# moire_v1_4-wip.net
KiCad netlist of a schematic drawn in EAGLE
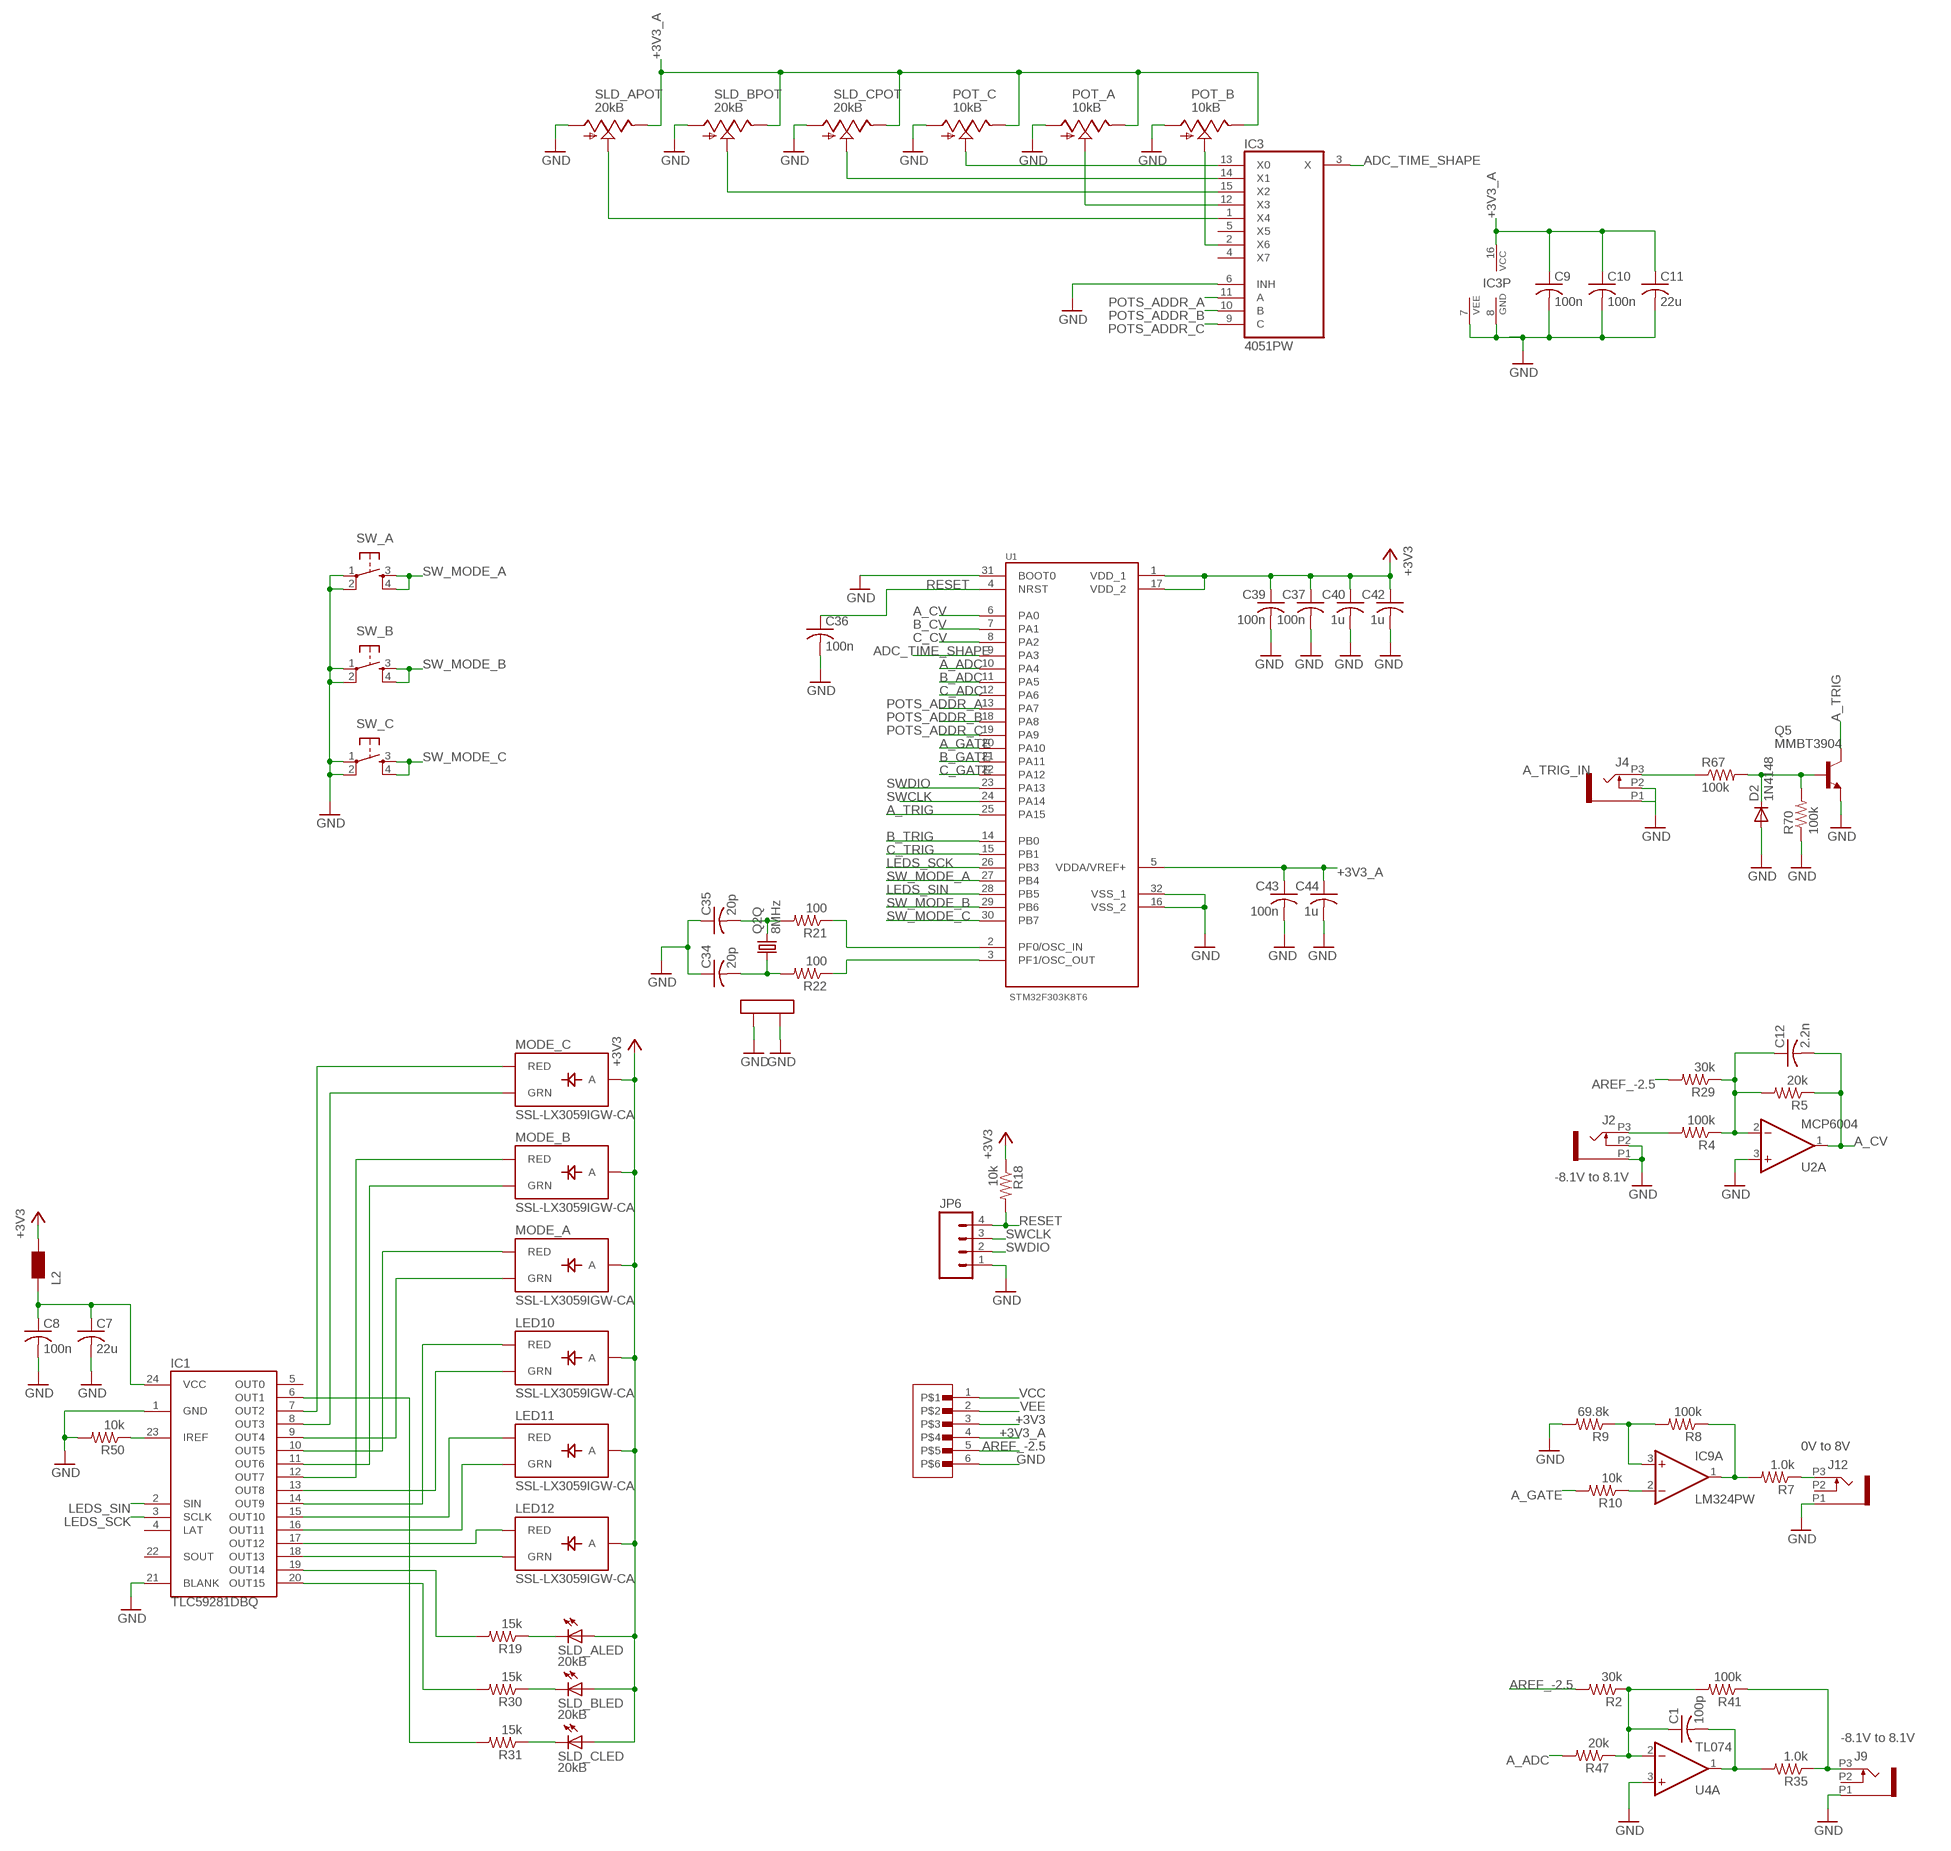
[diagram p0: schematic, sheet 1, part 1 of 2]
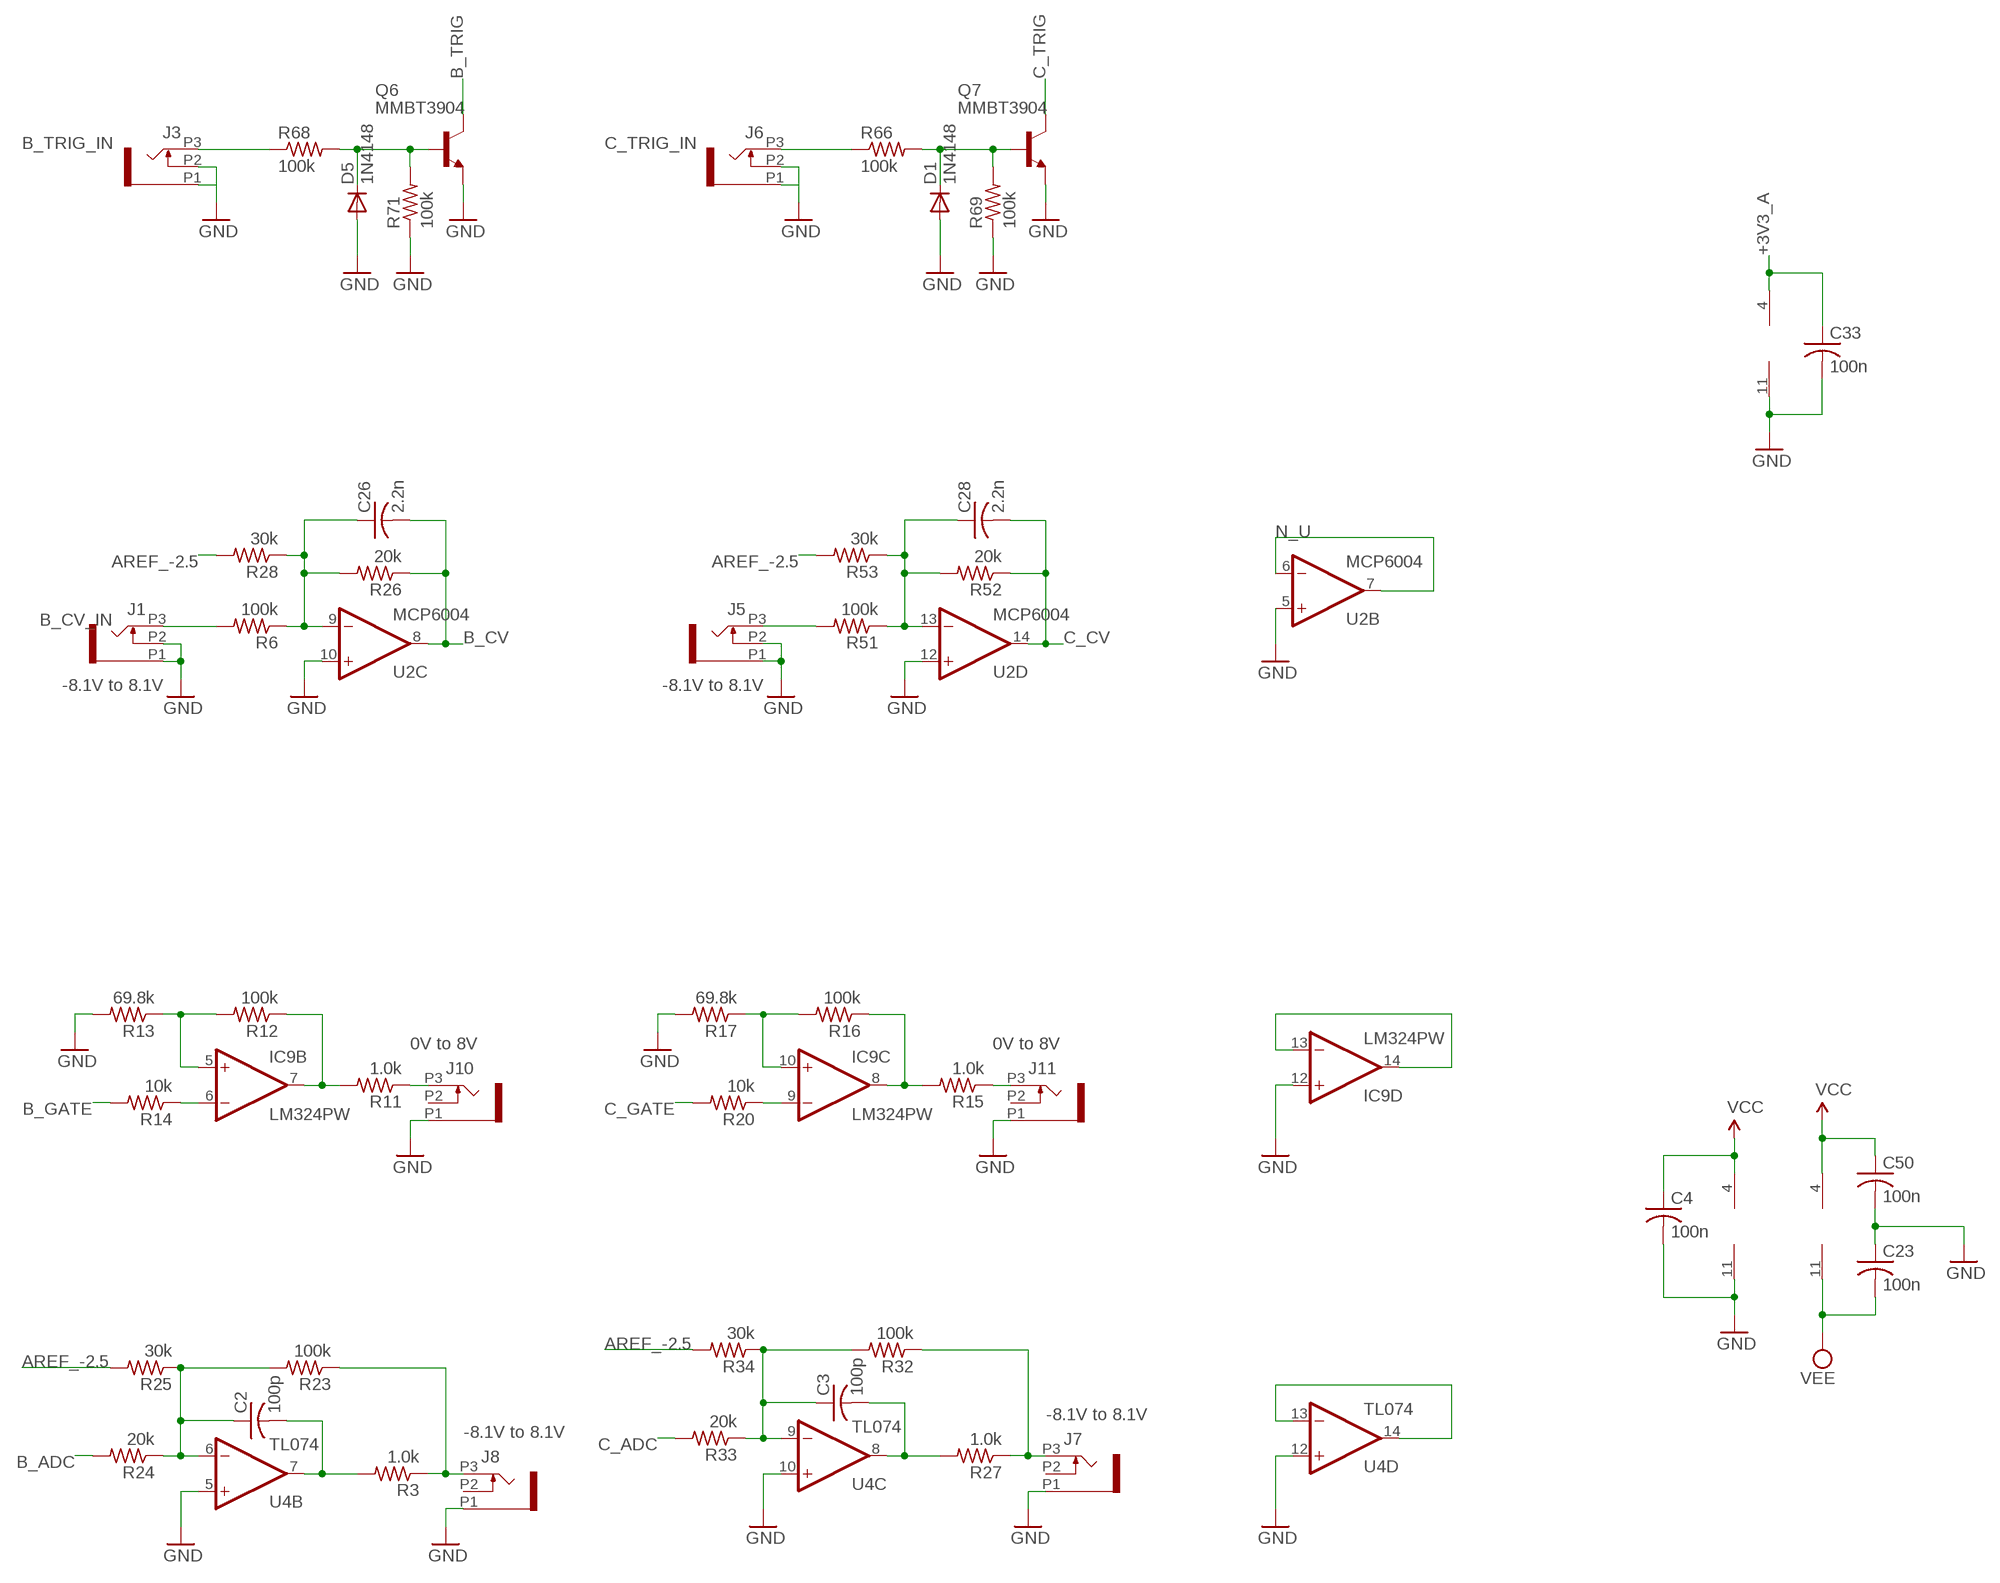
[diagram p1: schematic, sheet 1, part 2 of 2]
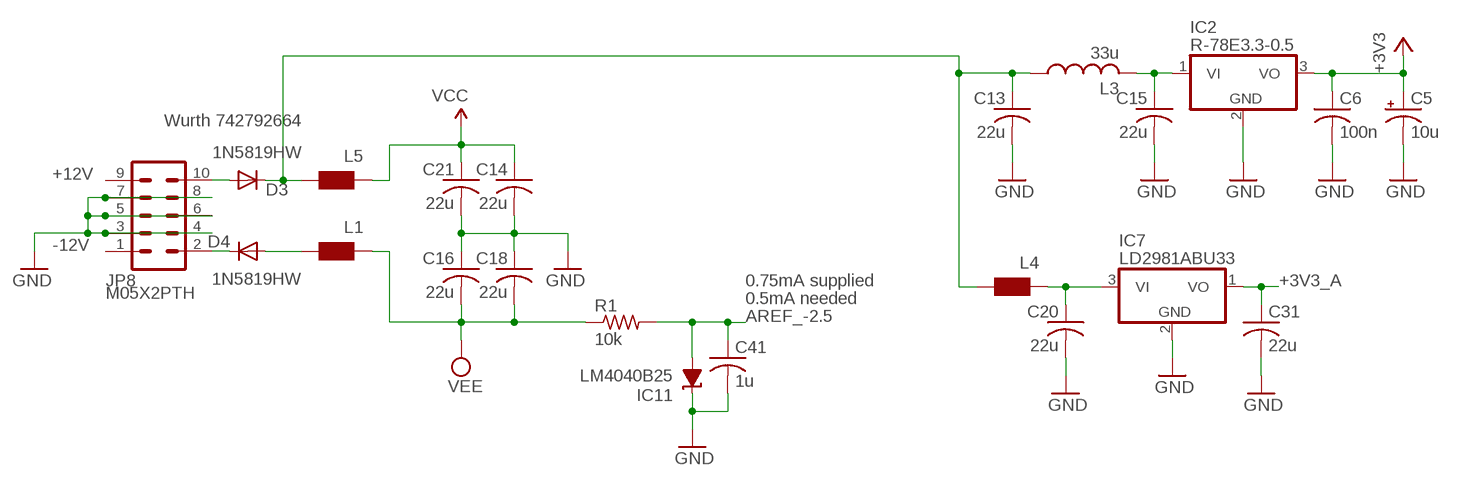
[diagram p2: schematic, sheet 2]

(export (version "E")
  (design (tool "Eeschema 10.0.6"))
  (components
    (comp (ref "C5")
      (value "10u")
      (footprint "eagle-import:PANASONIC_A")
      (libsource (lib "eagle-import") (part "CPOL-USA"))
    )
    (comp (ref "C6")
      (value "100n")
      (footprint "eagle-import:C0603")
      (libsource (lib "eagle-import") (part "C-USC0603"))
    )
    (comp (ref "C13")
      (value "22u")
      (footprint "eagle-import:C1206")
      (libsource (lib "eagle-import") (part "C-USC1206"))
    )
    (comp (ref "C14")
      (value "22u")
      (footprint "eagle-import:C1206")
      (libsource (lib "eagle-import") (part "C-USC1206"))
    )
    (comp (ref "C15")
      (value "22u")
      (footprint "eagle-import:C1206")
      (libsource (lib "eagle-import") (part "C-USC1206"))
    )
    (comp (ref "C16")
      (value "22u")
      (footprint "eagle-import:C1206")
      (libsource (lib "eagle-import") (part "C-USC1206"))
    )
    (comp (ref "C18")
      (value "22u")
      (footprint "eagle-import:C1206")
      (libsource (lib "eagle-import") (part "C-USC1206"))
    )
    (comp (ref "C20")
      (value "22u")
      (footprint "eagle-import:C1206")
      (libsource (lib "eagle-import") (part "C-USC1206"))
    )
    (comp (ref "C21")
      (value "22u")
      (footprint "eagle-import:C1206")
      (libsource (lib "eagle-import") (part "C-USC1206"))
    )
    (comp (ref "C31")
      (value "22u")
      (footprint "eagle-import:C1206")
      (libsource (lib "eagle-import") (part "C-USC1206"))
    )
    (comp (ref "C41")
      (value "1u")
      (footprint "eagle-import:C0603")
      (libsource (lib "eagle-import") (part "C-USC0603"))
    )
    (comp (ref "D3")
      (value "1N5819HW")
      (footprint "eagle-import:SOD123")
      (libsource (lib "eagle-import") (part "DIODE-SOD123"))
    )
    (comp (ref "D4")
      (value "1N5819HW")
      (footprint "eagle-import:SOD123")
      (libsource (lib "eagle-import") (part "DIODE-SOD123"))
    )
    (comp (ref "IC2")
      (value "R-78E3.3-0.5")
      (footprint "eagle-import:WE78")
      (libsource (lib "eagle-import") (part "WE173950378"))
    )
    (comp (ref "IC7")
      (value "LD2981ABU33")
      (footprint "eagle-import:SOT89")
      (libsource (lib "eagle-import") (part "LD2981ABU"))
    )
    (comp (ref "IC11")
      (value "LM4040B25")
      (footprint "eagle-import:DBZ_R-PDSO-G3")
      (libsource (lib "eagle-import") (part "LM4041DBZB12"))
    )
    (comp (ref "JP8")
      (value "M05X2PTH")
      (footprint "eagle-import:2X5-PTH")
      (libsource (lib "eagle-import") (part "M05X2PTH"))
    )
    (comp (ref "L1")
      (value "WE-CBF_0603")
      (footprint "eagle-import:0603")
      (libsource (lib "eagle-import") (part "WE-CBF_0603"))
    )
    (comp (ref "L3")
      (value "33u")
      (footprint "eagle-import:L2012C")
      (libsource (lib "eagle-import") (part "L-USL2012C"))
    )
    (comp (ref "L4")
      (value "WE-CBF_0603")
      (footprint "eagle-import:0603")
      (libsource (lib "eagle-import") (part "WE-CBF_0603"))
    )
    (comp (ref "L5")
      (value "WE-CBF_0603")
      (footprint "eagle-import:0603")
      (libsource (lib "eagle-import") (part "WE-CBF_0603"))
    )
    (comp (ref "R1")
      (value "10k")
      (footprint "eagle-import:R0603")
      (libsource (lib "eagle-import") (part "R-US_R0603"))
    )
    (comp (ref "C1")
      (value "100p")
      (footprint "eagle-import:C0603")
      (libsource (lib "eagle-import") (part "C-USC0603"))
    )
    (comp (ref "C2")
      (value "100p")
      (footprint "eagle-import:C0603")
      (libsource (lib "eagle-import") (part "C-USC0603"))
    )
    (comp (ref "C3")
      (value "100p")
      (footprint "eagle-import:C0603")
      (libsource (lib "eagle-import") (part "C-USC0603"))
    )
    (comp (ref "C4")
      (value "100n")
      (footprint "eagle-import:C0603")
      (libsource (lib "eagle-import") (part "C-USC0603"))
    )
    (comp (ref "C7")
      (value "22u")
      (footprint "eagle-import:C1206")
      (libsource (lib "eagle-import") (part "C-USC1206"))
    )
    (comp (ref "C8")
      (value "100n")
      (footprint "eagle-import:C0603")
      (libsource (lib "eagle-import") (part "C-USC0603"))
    )
    (comp (ref "C9")
      (value "100n")
      (footprint "eagle-import:C0603")
      (libsource (lib "eagle-import") (part "C-USC0603"))
    )
    (comp (ref "C10")
      (value "100n")
      (footprint "eagle-import:C0603")
      (libsource (lib "eagle-import") (part "C-USC0603"))
    )
    (comp (ref "C11")
      (value "22u")
      (footprint "eagle-import:C1206")
      (libsource (lib "eagle-import") (part "C-USC1206"))
    )
    (comp (ref "C12")
      (value "2.2n")
      (footprint "eagle-import:C0603")
      (libsource (lib "eagle-import") (part "C-USC0603"))
    )
    (comp (ref "C23")
      (value "100n")
      (footprint "eagle-import:C0603")
      (libsource (lib "eagle-import") (part "C-USC0603"))
    )
    (comp (ref "C26")
      (value "2.2n")
      (footprint "eagle-import:C0603")
      (libsource (lib "eagle-import") (part "C-USC0603"))
    )
    (comp (ref "C28")
      (value "2.2n")
      (footprint "eagle-import:C0603")
      (libsource (lib "eagle-import") (part "C-USC0603"))
    )
    (comp (ref "C33")
      (value "100n")
      (footprint "eagle-import:C0603")
      (libsource (lib "eagle-import") (part "C-USC0603"))
    )
    (comp (ref "C34")
      (value "20p")
      (footprint "eagle-import:C0603")
      (libsource (lib "eagle-import") (part "C-USC0603"))
    )
    (comp (ref "C35")
      (value "20p")
      (footprint "eagle-import:C0603")
      (libsource (lib "eagle-import") (part "C-USC0603"))
    )
    (comp (ref "C36")
      (value "100n")
      (footprint "eagle-import:C0603")
      (libsource (lib "eagle-import") (part "C-USC0603"))
    )
    (comp (ref "C37")
      (value "100n")
      (footprint "eagle-import:C0603")
      (libsource (lib "eagle-import") (part "C-USC0603"))
    )
    (comp (ref "C39")
      (value "100n")
      (footprint "eagle-import:C0603")
      (libsource (lib "eagle-import") (part "C-USC0603"))
    )
    (comp (ref "C40")
      (value "1u")
      (footprint "eagle-import:C0603")
      (libsource (lib "eagle-import") (part "C-USC0603"))
    )
    (comp (ref "C42")
      (value "1u")
      (footprint "eagle-import:C0603")
      (libsource (lib "eagle-import") (part "C-USC0603"))
    )
    (comp (ref "C43")
      (value "100n")
      (footprint "eagle-import:C0603")
      (libsource (lib "eagle-import") (part "C-USC0603"))
    )
    (comp (ref "C44")
      (value "1u")
      (footprint "eagle-import:C0603")
      (libsource (lib "eagle-import") (part "C-USC0603"))
    )
    (comp (ref "C50")
      (value "100n")
      (footprint "eagle-import:C0603")
      (libsource (lib "eagle-import") (part "C-USC0603"))
    )
    (comp (ref "D1")
      (value "1N4148")
      (footprint "eagle-import:SOD523")
      (libsource (lib "eagle-import") (part "DIODE-SOD523"))
    )
    (comp (ref "D2")
      (value "1N4148")
      (footprint "eagle-import:SOD523")
      (libsource (lib "eagle-import") (part "DIODE-SOD523"))
    )
    (comp (ref "D5")
      (value "1N4148")
      (footprint "eagle-import:SOD523")
      (libsource (lib "eagle-import") (part "DIODE-SOD523"))
    )
    (comp (ref "IC1")
      (value "TLC59281DBQ")
      (footprint "eagle-import:TSSOP24_0635")
      (libsource (lib "eagle-import") (part "TLC59281DBQ"))
    )
    (comp (ref "IC3")
      (value "4051PW")
      (footprint "eagle-import:TSSOP16_065")
      (libsource (lib "eagle-import") (part "4051PW"))
    )
    (comp (ref "IC9")
      (value "LM324PW")
      (footprint "eagle-import:TSSOP14_065")
      (libsource (lib "eagle-import") (part "TL074PW"))
    )
    (comp (ref "J1")
      (value "PJ301_THONKICONN6")
      (footprint "eagle-import:WQP_PJ_301M6")
      (libsource (lib "eagle-import") (part "PJ301_THONKICONN6"))
    )
    (comp (ref "J2")
      (value "PJ301_THONKICONN6")
      (footprint "eagle-import:WQP_PJ_301M6")
      (libsource (lib "eagle-import") (part "PJ301_THONKICONN6"))
    )
    (comp (ref "J3")
      (value "PJ301_THONKICONN6")
      (footprint "eagle-import:WQP_PJ_301M6")
      (libsource (lib "eagle-import") (part "PJ301_THONKICONN6"))
    )
    (comp (ref "J4")
      (value "PJ301_THONKICONN6")
      (footprint "eagle-import:WQP_PJ_301M6")
      (libsource (lib "eagle-import") (part "PJ301_THONKICONN6"))
    )
    (comp (ref "J5")
      (value "PJ301_THONKICONN6")
      (footprint "eagle-import:WQP_PJ_301M6")
      (libsource (lib "eagle-import") (part "PJ301_THONKICONN6"))
    )
    (comp (ref "J6")
      (value "PJ301_THONKICONN6")
      (footprint "eagle-import:WQP_PJ_301M6")
      (libsource (lib "eagle-import") (part "PJ301_THONKICONN6"))
    )
    (comp (ref "J7")
      (value "PJ301_THONKICONN6")
      (footprint "eagle-import:WQP_PJ_301M6")
      (libsource (lib "eagle-import") (part "PJ301_THONKICONN6"))
    )
    (comp (ref "J8")
      (value "PJ301_THONKICONN6")
      (footprint "eagle-import:WQP_PJ_301M6")
      (libsource (lib "eagle-import") (part "PJ301_THONKICONN6"))
    )
    (comp (ref "J9")
      (value "PJ301_THONKICONN6")
      (footprint "eagle-import:WQP_PJ_301M6")
      (libsource (lib "eagle-import") (part "PJ301_THONKICONN6"))
    )
    (comp (ref "J10")
      (value "PJ301_THONKICONN6")
      (footprint "eagle-import:WQP_PJ_301M6")
      (libsource (lib "eagle-import") (part "PJ301_THONKICONN6"))
    )
    (comp (ref "J11")
      (value "PJ301_THONKICONN6")
      (footprint "eagle-import:WQP_PJ_301M6")
      (libsource (lib "eagle-import") (part "PJ301_THONKICONN6"))
    )
    (comp (ref "J12")
      (value "PJ301_THONKICONN6")
      (footprint "eagle-import:WQP_PJ_301M6")
      (libsource (lib "eagle-import") (part "PJ301_THONKICONN6"))
    )
    (comp (ref "JP6")
      (value "M04PTH")
      (footprint "eagle-import:1X04")
      (libsource (lib "eagle-import") (part "M04PTH"))
    )
    (comp (ref "L2")
      (value "WE-CBF_0603")
      (footprint "eagle-import:0603")
      (libsource (lib "eagle-import") (part "WE-CBF_0603"))
    )
    (comp (ref "LED10")
      (value "SSL-LX3059IGW-CA")
      (footprint "eagle-import:LED-BICOLOR-THROUGHHOLE-LUMEX")
      (libsource (lib "eagle-import") (part "LED-BICOLOR-THROUGHHOLE-CA"))
    )
    (comp (ref "LED11")
      (value "SSL-LX3059IGW-CA")
      (footprint "eagle-import:LED-BICOLOR-THROUGHHOLE-LUMEX")
      (libsource (lib "eagle-import") (part "LED-BICOLOR-THROUGHHOLE-CA"))
    )
    (comp (ref "LED12")
      (value "SSL-LX3059IGW-CA")
      (footprint "eagle-import:LED-BICOLOR-THROUGHHOLE-LUMEX")
      (libsource (lib "eagle-import") (part "LED-BICOLOR-THROUGHHOLE-CA"))
    )
    (comp (ref "MODE_A")
      (value "SSL-LX3059IGW-CA")
      (footprint "eagle-import:LED-BICOLOR-THROUGHHOLE-LUMEX")
      (libsource (lib "eagle-import") (part "LED-BICOLOR-THROUGHHOLE-CA"))
    )
    (comp (ref "MODE_B")
      (value "SSL-LX3059IGW-CA")
      (footprint "eagle-import:LED-BICOLOR-THROUGHHOLE-LUMEX")
      (libsource (lib "eagle-import") (part "LED-BICOLOR-THROUGHHOLE-CA"))
    )
    (comp (ref "MODE_C")
      (value "SSL-LX3059IGW-CA")
      (footprint "eagle-import:LED-BICOLOR-THROUGHHOLE-LUMEX")
      (libsource (lib "eagle-import") (part "LED-BICOLOR-THROUGHHOLE-CA"))
    )
    (comp (ref "POT_A")
      (value "10kB")
      (footprint "eagle-import:ALPS_POT_VERTICAL")
      (libsource (lib "eagle-import") (part "POT_USVERTICAL"))
    )
    (comp (ref "POT_B")
      (value "10kB")
      (footprint "eagle-import:ALPS_POT_VERTICAL")
      (libsource (lib "eagle-import") (part "POT_USVERTICAL"))
    )
    (comp (ref "POT_C")
      (value "10kB")
      (footprint "eagle-import:ALPS_POT_VERTICAL")
      (libsource (lib "eagle-import") (part "POT_USVERTICAL"))
    )
    (comp (ref "Q2")
      (value "8MHz")
      (footprint "eagle-import:CTS406")
      (libsource (lib "eagle-import") (part "CRYSTAL"))
    )
    (comp (ref "Q5")
      (value "MMBT3904")
      (footprint "eagle-import:SOT23-BEC")
      (libsource (lib "eagle-import") (part "-NPN-SOT23-BECMMBT3904LT1"))
    )
    (comp (ref "Q6")
      (value "MMBT3904")
      (footprint "eagle-import:SOT23-BEC")
      (libsource (lib "eagle-import") (part "-NPN-SOT23-BECMMBT3904LT1"))
    )
    (comp (ref "Q7")
      (value "MMBT3904")
      (footprint "eagle-import:SOT23-BEC")
      (libsource (lib "eagle-import") (part "-NPN-SOT23-BECMMBT3904LT1"))
    )
    (comp (ref "R2")
      (value "30k")
      (footprint "eagle-import:R0603")
      (libsource (lib "eagle-import") (part "R-US_R0603"))
    )
    (comp (ref "R3")
      (value "1.0k")
      (footprint "eagle-import:R0603")
      (libsource (lib "eagle-import") (part "R-US_R0603"))
    )
    (comp (ref "R4")
      (value "100k")
      (footprint "eagle-import:R0603")
      (libsource (lib "eagle-import") (part "R-US_R0603"))
    )
    (comp (ref "R5")
      (value "20k")
      (footprint "eagle-import:R0603")
      (libsource (lib "eagle-import") (part "R-US_R0603"))
    )
    (comp (ref "R6")
      (value "100k")
      (footprint "eagle-import:R0603")
      (libsource (lib "eagle-import") (part "R-US_R0603"))
    )
    (comp (ref "R7")
      (value "1.0k")
      (footprint "eagle-import:R0603")
      (libsource (lib "eagle-import") (part "R-US_R0603"))
    )
    (comp (ref "R8")
      (value "100k")
      (footprint "eagle-import:R0603")
      (libsource (lib "eagle-import") (part "R-US_R0603"))
    )
    (comp (ref "R9")
      (value "69.8k")
      (footprint "eagle-import:R0603")
      (libsource (lib "eagle-import") (part "R-US_R0603"))
    )
    (comp (ref "R10")
      (value "10k")
      (footprint "eagle-import:R0603")
      (libsource (lib "eagle-import") (part "R-US_R0603"))
    )
    (comp (ref "R11")
      (value "1.0k")
      (footprint "eagle-import:R0603")
      (libsource (lib "eagle-import") (part "R-US_R0603"))
    )
    (comp (ref "R12")
      (value "100k")
      (footprint "eagle-import:R0603")
      (libsource (lib "eagle-import") (part "R-US_R0603"))
    )
    (comp (ref "R13")
      (value "69.8k")
      (footprint "eagle-import:R0603")
      (libsource (lib "eagle-import") (part "R-US_R0603"))
    )
    (comp (ref "R14")
      (value "10k")
      (footprint "eagle-import:R0603")
      (libsource (lib "eagle-import") (part "R-US_R0603"))
    )
    (comp (ref "R15")
      (value "1.0k")
      (footprint "eagle-import:R0603")
      (libsource (lib "eagle-import") (part "R-US_R0603"))
    )
    (comp (ref "R16")
      (value "100k")
      (footprint "eagle-import:R0603")
      (libsource (lib "eagle-import") (part "R-US_R0603"))
    )
    (comp (ref "R17")
      (value "69.8k")
      (footprint "eagle-import:R0603")
      (libsource (lib "eagle-import") (part "R-US_R0603"))
    )
    (comp (ref "R18")
      (value "10k")
      (footprint "eagle-import:R0603")
      (libsource (lib "eagle-import") (part "R-US_R0603"))
    )
    (comp (ref "R19")
      (value "15k")
      (footprint "eagle-import:R0603")
      (libsource (lib "eagle-import") (part "R-US_R0603"))
    )
    (comp (ref "R20")
      (value "10k")
      (footprint "eagle-import:R0603")
      (libsource (lib "eagle-import") (part "R-US_R0603"))
    )
    (comp (ref "R21")
      (value "100")
      (footprint "eagle-import:R0603")
      (libsource (lib "eagle-import") (part "R-US_R0603"))
    )
    (comp (ref "R22")
      (value "100")
      (footprint "eagle-import:R0603")
      (libsource (lib "eagle-import") (part "R-US_R0603"))
    )
    (comp (ref "R23")
      (value "100k")
      (footprint "eagle-import:R0603")
      (libsource (lib "eagle-import") (part "R-US_R0603"))
    )
    (comp (ref "R24")
      (value "20k")
      (footprint "eagle-import:R0603")
      (libsource (lib "eagle-import") (part "R-US_R0603"))
    )
    (comp (ref "R25")
      (value "30k")
      (footprint "eagle-import:R0603")
      (libsource (lib "eagle-import") (part "R-US_R0603"))
    )
    (comp (ref "R26")
      (value "20k")
      (footprint "eagle-import:R0603")
      (libsource (lib "eagle-import") (part "R-US_R0603"))
    )
    (comp (ref "R27")
      (value "1.0k")
      (footprint "eagle-import:R0603")
      (libsource (lib "eagle-import") (part "R-US_R0603"))
    )
    (comp (ref "R28")
      (value "30k")
      (footprint "eagle-import:R0603")
      (libsource (lib "eagle-import") (part "R-US_R0603"))
    )
    (comp (ref "R29")
      (value "30k")
      (footprint "eagle-import:R0603")
      (libsource (lib "eagle-import") (part "R-US_R0603"))
    )
    (comp (ref "R30")
      (value "15k")
      (footprint "eagle-import:R0603")
      (libsource (lib "eagle-import") (part "R-US_R0603"))
    )
    (comp (ref "R31")
      (value "15k")
      (footprint "eagle-import:R0603")
      (libsource (lib "eagle-import") (part "R-US_R0603"))
    )
    (comp (ref "R32")
      (value "100k")
      (footprint "eagle-import:R0603")
      (libsource (lib "eagle-import") (part "R-US_R0603"))
    )
    (comp (ref "R33")
      (value "20k")
      (footprint "eagle-import:R0603")
      (libsource (lib "eagle-import") (part "R-US_R0603"))
    )
    (comp (ref "R34")
      (value "30k")
      (footprint "eagle-import:R0603")
      (libsource (lib "eagle-import") (part "R-US_R0603"))
    )
    (comp (ref "R35")
      (value "1.0k")
      (footprint "eagle-import:R0603")
      (libsource (lib "eagle-import") (part "R-US_R0603"))
    )
    (comp (ref "R41")
      (value "100k")
      (footprint "eagle-import:R0603")
      (libsource (lib "eagle-import") (part "R-US_R0603"))
    )
    (comp (ref "R47")
      (value "20k")
      (footprint "eagle-import:R0603")
      (libsource (lib "eagle-import") (part "R-US_R0603"))
    )
    (comp (ref "R50")
      (value "10k")
      (footprint "eagle-import:R0603")
      (libsource (lib "eagle-import") (part "R-US_R0603"))
    )
    (comp (ref "R51")
      (value "100k")
      (footprint "eagle-import:R0603")
      (libsource (lib "eagle-import") (part "R-US_R0603"))
    )
    (comp (ref "R52")
      (value "20k")
      (footprint "eagle-import:R0603")
      (libsource (lib "eagle-import") (part "R-US_R0603"))
    )
    (comp (ref "R53")
      (value "30k")
      (footprint "eagle-import:R0603")
      (libsource (lib "eagle-import") (part "R-US_R0603"))
    )
    (comp (ref "R66")
      (value "100k")
      (footprint "eagle-import:R0603")
      (libsource (lib "eagle-import") (part "R-US_R0603"))
    )
    (comp (ref "R67")
      (value "100k")
      (footprint "eagle-import:R0603")
      (libsource (lib "eagle-import") (part "R-US_R0603"))
    )
    (comp (ref "R68")
      (value "100k")
      (footprint "eagle-import:R0603")
      (libsource (lib "eagle-import") (part "R-US_R0603"))
    )
    (comp (ref "R69")
      (value "100k")
      (footprint "eagle-import:R0603")
      (libsource (lib "eagle-import") (part "R-US_R0603"))
    )
    (comp (ref "R70")
      (value "100k")
      (footprint "eagle-import:R0603")
      (libsource (lib "eagle-import") (part "R-US_R0603"))
    )
    (comp (ref "R71")
      (value "100k")
      (footprint "eagle-import:R0603")
      (libsource (lib "eagle-import") (part "R-US_R0603"))
    )
    (comp (ref "SLD_A")
      (value "20kB")
      (footprint "eagle-import:BOURNS_SLIDER")
      (libsource (lib "eagle-import") (part "BOURNS_SLIDER"))
    )
    (comp (ref "SLD_B")
      (value "20kB")
      (footprint "eagle-import:BOURNS_SLIDER")
      (libsource (lib "eagle-import") (part "BOURNS_SLIDER"))
    )
    (comp (ref "SLD_C")
      (value "20kB")
      (footprint "eagle-import:BOURNS_SLIDER")
      (libsource (lib "eagle-import") (part "BOURNS_SLIDER"))
    )
    (comp (ref "SW_A")
      (value "TAC_SWITCHPTH")
      (footprint "eagle-import:TACTILE-PTH")
      (libsource (lib "eagle-import") (part "TAC_SWITCHPTH"))
    )
    (comp (ref "SW_B")
      (value "TAC_SWITCHPTH")
      (footprint "eagle-import:TACTILE-PTH")
      (libsource (lib "eagle-import") (part "TAC_SWITCHPTH"))
    )
    (comp (ref "SW_C")
      (value "TAC_SWITCHPTH")
      (footprint "eagle-import:TACTILE-PTH")
      (libsource (lib "eagle-import") (part "TAC_SWITCHPTH"))
    )
    (comp (ref "U$1")
      (value "1X6-SMD-TESTPAD")
      (footprint "eagle-import:6X1-SMD-TESTPAD")
      (libsource (lib "eagle-import") (part "1X6-SMD-TESTPAD"))
    )
    (comp (ref "U1")
      (value "STM32F303K8T6")
      (footprint "eagle-import:QFP80P900X900X160-32N")
      (fields (field (name "MF") "STMicroelectronics"))
      (libsource (lib "eagle-import") (part "STM32F303K8T6"))
    )
    (comp (ref "U2")
      (value "MCP6004")
      (footprint "eagle-import:SO14")
      (libsource (lib "eagle-import") (part "MCP6004_SMD"))
    )
    (comp (ref "U4")
      (value "TL074")
      (footprint "eagle-import:SO14")
      (libsource (lib "eagle-import") (part "TL074_SMD"))
    )
  )
  (nets
    (net (code "1") (name "+3V3") (class "Default")
      (node (ref "C37") (pin "1") (pinfunction "1_1") (pintype "passive"))
      (node (ref "C39") (pin "1") (pinfunction "1_1") (pintype "passive"))
      (node (ref "C40") (pin "1") (pinfunction "1_1") (pintype "passive"))
      (node (ref "C42") (pin "1") (pinfunction "1_1") (pintype "passive"))
      (node (ref "C5") (pin "+") (pinfunction "+_+") (pintype "passive"))
      (node (ref "C6") (pin "1") (pinfunction "1_1") (pintype "passive"))
      (node (ref "IC2") (pin "3") (pinfunction "VO_3") (pintype "passive"))
      (node (ref "L2") (pin "2") (pinfunction "2_2") (pintype "passive"))
      (node (ref "LED10") (pin "A") (pinfunction "A_A") (pintype "bidirectional"))
      (node (ref "LED11") (pin "A") (pinfunction "A_A") (pintype "bidirectional"))
      (node (ref "LED12") (pin "A") (pinfunction "A_A") (pintype "bidirectional"))
      (node (ref "MODE_A") (pin "A") (pinfunction "A_A") (pintype "bidirectional"))
      (node (ref "MODE_B") (pin "A") (pinfunction "A_A") (pintype "bidirectional"))
      (node (ref "MODE_C") (pin "A") (pinfunction "A_A") (pintype "bidirectional"))
      (node (ref "R18") (pin "1") (pinfunction "1_1") (pintype "passive"))
      (node (ref "SLD_A") (pin "B") (pinfunction "A_B") (pintype "passive"))
      (node (ref "SLD_B") (pin "B") (pinfunction "A_B") (pintype "passive"))
      (node (ref "SLD_C") (pin "B") (pinfunction "A_B") (pintype "passive"))
      (node (ref "U$1") (pin "3") (pinfunction "P$3_3") (pintype "bidirectional"))
      (node (ref "U1") (pin "1") (pinfunction "VDD_1_1") (pintype "power_in"))
      (node (ref "U1") (pin "17") (pinfunction "VDD_2_17") (pintype "power_in"))
    )
    (net (code "2") (name "+3V3_A") (class "Default")
      (node (ref "C10") (pin "1") (pinfunction "1_1") (pintype "passive"))
      (node (ref "C11") (pin "1") (pinfunction "1_1") (pintype "passive"))
      (node (ref "C31") (pin "1") (pinfunction "1_1") (pintype "passive"))
      (node (ref "C33") (pin "1") (pinfunction "1_1") (pintype "passive"))
      (node (ref "C43") (pin "1") (pinfunction "1_1") (pintype "passive"))
      (node (ref "C44") (pin "1") (pinfunction "1_1") (pintype "passive"))
      (node (ref "C9") (pin "1") (pinfunction "1_1") (pintype "passive"))
      (node (ref "IC3") (pin "16") (pinfunction "VCC_16") (pintype "power_in"))
      (node (ref "IC7") (pin "1") (pinfunction "VO_1") (pintype "passive"))
      (node (ref "POT_A") (pin "P$1") (pinfunction "E_P$1") (pintype "passive"))
      (node (ref "POT_B") (pin "P$1") (pinfunction "E_P$1") (pintype "passive"))
      (node (ref "POT_C") (pin "P$1") (pinfunction "E_P$1") (pintype "passive"))
      (node (ref "SLD_A") (pin "3") (pinfunction "E_3") (pintype "passive"))
      (node (ref "SLD_B") (pin "3") (pinfunction "E_3") (pintype "passive"))
      (node (ref "SLD_C") (pin "3") (pinfunction "E_3") (pintype "passive"))
      (node (ref "U$1") (pin "4") (pinfunction "P$4_4") (pintype "bidirectional"))
      (node (ref "U1") (pin "5") (pinfunction "VDDA/VREF+_5") (pintype "power_in"))
      (node (ref "U2") (pin "4") (pinfunction "V+_4") (pintype "power_in"))
    )
    (net (code "3") (name "+12V") (class "Default")
      (node (ref "D3") (pin "A") (pinfunction "A_A") (pintype "passive"))
      (node (ref "JP8") (pin "10") (pinfunction "10_10") (pintype "passive"))
      (node (ref "JP8") (pin "9") (pinfunction "9_9") (pintype "passive"))
    )
    (net (code "4") (name "-12V") (class "Default")
      (node (ref "D4") (pin "C") (pinfunction "C_C") (pintype "passive"))
      (node (ref "JP8") (pin "1") (pinfunction "1_1") (pintype "passive"))
      (node (ref "JP8") (pin "2") (pinfunction "2_2") (pintype "passive"))
    )
    (net (code "5") (name "ADC_TIME_SHAPE") (class "Default")
      (node (ref "IC3") (pin "3") (pinfunction "X_3") (pintype "bidirectional"))
      (node (ref "U1") (pin "9") (pinfunction "PA3_9") (pintype "bidirectional"))
    )
    (net (code "6") (name "AREF_-2.5") (class "Default")
      (node (ref "C41") (pin "1") (pinfunction "1_1") (pintype "passive"))
      (node (ref "IC11") (pin "2") (pinfunction "A_2") (pintype "passive"))
      (node (ref "R1") (pin "2") (pinfunction "2_2") (pintype "passive"))
      (node (ref "R2") (pin "2") (pinfunction "2_2") (pintype "passive"))
      (node (ref "R25") (pin "2") (pinfunction "2_2") (pintype "passive"))
      (node (ref "R28") (pin "2") (pinfunction "2_2") (pintype "passive"))
      (node (ref "R29") (pin "2") (pinfunction "2_2") (pintype "passive"))
      (node (ref "R34") (pin "2") (pinfunction "2_2") (pintype "passive"))
      (node (ref "R53") (pin "2") (pinfunction "2_2") (pintype "passive"))
      (node (ref "U$1") (pin "5") (pinfunction "P$5_5") (pintype "bidirectional"))
    )
    (net (code "7") (name "A_ADC") (class "Default")
      (node (ref "R47") (pin "2") (pinfunction "2_2") (pintype "passive"))
      (node (ref "U1") (pin "10") (pinfunction "PA4_10") (pintype "bidirectional"))
    )
    (net (code "8") (name "A_CV") (class "Default")
      (node (ref "C12") (pin "2") (pinfunction "2_2") (pintype "passive"))
      (node (ref "R5") (pin "1") (pinfunction "1_1") (pintype "passive"))
      (node (ref "U1") (pin "6") (pinfunction "PA0_6") (pintype "bidirectional"))
      (node (ref "U2") (pin "1") (pinfunction "OUT_1") (pintype "output"))
    )
    (net (code "9") (name "A_GATE") (class "Default")
      (node (ref "R10") (pin "2") (pinfunction "2_2") (pintype "passive"))
      (node (ref "U1") (pin "20") (pinfunction "PA10_20") (pintype "bidirectional"))
    )
    (net (code "10") (name "A_TRIG") (class "Default")
      (node (ref "Q5") (pin "C") (pinfunction "C_C") (pintype "passive"))
      (node (ref "U1") (pin "25") (pinfunction "PA15_25") (pintype "bidirectional"))
    )
    (net (code "11") (name "A_TRIG_IN") (class "Default")
      (node (ref "J4") (pin "P3") (pinfunction "3_P3") (pintype "passive"))
      (node (ref "R67") (pin "1") (pinfunction "1_1") (pintype "passive"))
    )
    (net (code "12") (name "B_ADC") (class "Default")
      (node (ref "R24") (pin "2") (pinfunction "2_2") (pintype "passive"))
      (node (ref "U1") (pin "11") (pinfunction "PA5_11") (pintype "bidirectional"))
    )
    (net (code "13") (name "B_CV") (class "Default")
      (node (ref "C26") (pin "2") (pinfunction "2_2") (pintype "passive"))
      (node (ref "R26") (pin "1") (pinfunction "1_1") (pintype "passive"))
      (node (ref "U1") (pin "7") (pinfunction "PA1_7") (pintype "bidirectional"))
      (node (ref "U2") (pin "8") (pinfunction "OUT_8") (pintype "output"))
    )
    (net (code "14") (name "B_CV_IN") (class "Default")
      (node (ref "J1") (pin "P3") (pinfunction "3_P3") (pintype "passive"))
      (node (ref "R6") (pin "2") (pinfunction "2_2") (pintype "passive"))
    )
    (net (code "15") (name "B_GATE") (class "Default")
      (node (ref "R14") (pin "2") (pinfunction "2_2") (pintype "passive"))
      (node (ref "U1") (pin "21") (pinfunction "PA11_21") (pintype "bidirectional"))
    )
    (net (code "16") (name "B_TRIG") (class "Default")
      (node (ref "Q6") (pin "C") (pinfunction "C_C") (pintype "passive"))
      (node (ref "U1") (pin "14") (pinfunction "PB0_14") (pintype "bidirectional"))
    )
    (net (code "17") (name "B_TRIG_IN") (class "Default")
      (node (ref "J3") (pin "P3") (pinfunction "3_P3") (pintype "passive"))
      (node (ref "R68") (pin "1") (pinfunction "1_1") (pintype "passive"))
    )
    (net (code "18") (name "C_ADC") (class "Default")
      (node (ref "R33") (pin "2") (pinfunction "2_2") (pintype "passive"))
      (node (ref "U1") (pin "12") (pinfunction "PA6_12") (pintype "bidirectional"))
    )
    (net (code "19") (name "C_CV") (class "Default")
      (node (ref "C28") (pin "2") (pinfunction "2_2") (pintype "passive"))
      (node (ref "R52") (pin "1") (pinfunction "1_1") (pintype "passive"))
      (node (ref "U1") (pin "8") (pinfunction "PA2_8") (pintype "bidirectional"))
      (node (ref "U2") (pin "14") (pinfunction "OUT_14") (pintype "output"))
    )
    (net (code "20") (name "C_GATE") (class "Default")
      (node (ref "R20") (pin "2") (pinfunction "2_2") (pintype "passive"))
      (node (ref "U1") (pin "22") (pinfunction "PA12_22") (pintype "bidirectional"))
    )
    (net (code "21") (name "C_TRIG") (class "Default")
      (node (ref "Q7") (pin "C") (pinfunction "C_C") (pintype "passive"))
      (node (ref "U1") (pin "15") (pinfunction "PB1_15") (pintype "bidirectional"))
    )
    (net (code "22") (name "C_TRIG_IN") (class "Default")
      (node (ref "J6") (pin "P3") (pinfunction "3_P3") (pintype "passive"))
      (node (ref "R66") (pin "1") (pinfunction "1_1") (pintype "passive"))
    )
    (net (code "23") (name "GND") (class "Default")
      (node (ref "C10") (pin "2") (pinfunction "2_2") (pintype "passive"))
      (node (ref "C11") (pin "2") (pinfunction "2_2") (pintype "passive"))
      (node (ref "C13") (pin "2") (pinfunction "2_2") (pintype "passive"))
      (node (ref "C14") (pin "2") (pinfunction "2_2") (pintype "passive"))
      (node (ref "C15") (pin "2") (pinfunction "2_2") (pintype "passive"))
      (node (ref "C16") (pin "1") (pinfunction "1_1") (pintype "passive"))
      (node (ref "C18") (pin "1") (pinfunction "1_1") (pintype "passive"))
      (node (ref "C20") (pin "2") (pinfunction "2_2") (pintype "passive"))
      (node (ref "C21") (pin "2") (pinfunction "2_2") (pintype "passive"))
      (node (ref "C23") (pin "1") (pinfunction "1_1") (pintype "passive"))
      (node (ref "C31") (pin "2") (pinfunction "2_2") (pintype "passive"))
      (node (ref "C33") (pin "2") (pinfunction "2_2") (pintype "passive"))
      (node (ref "C34") (pin "1") (pinfunction "1_1") (pintype "passive"))
      (node (ref "C35") (pin "1") (pinfunction "1_1") (pintype "passive"))
      (node (ref "C36") (pin "2") (pinfunction "2_2") (pintype "passive"))
      (node (ref "C37") (pin "2") (pinfunction "2_2") (pintype "passive"))
      (node (ref "C39") (pin "2") (pinfunction "2_2") (pintype "passive"))
      (node (ref "C4") (pin "2") (pinfunction "2_2") (pintype "passive"))
      (node (ref "C40") (pin "2") (pinfunction "2_2") (pintype "passive"))
      (node (ref "C41") (pin "2") (pinfunction "2_2") (pintype "passive"))
      (node (ref "C42") (pin "2") (pinfunction "2_2") (pintype "passive"))
      (node (ref "C43") (pin "2") (pinfunction "2_2") (pintype "passive"))
      (node (ref "C44") (pin "2") (pinfunction "2_2") (pintype "passive"))
      (node (ref "C5") (pin "-") (pinfunction "-_-") (pintype "passive"))
      (node (ref "C50") (pin "2") (pinfunction "2_2") (pintype "passive"))
      (node (ref "C6") (pin "2") (pinfunction "2_2") (pintype "passive"))
      (node (ref "C7") (pin "2") (pinfunction "2_2") (pintype "passive"))
      (node (ref "C8") (pin "2") (pinfunction "2_2") (pintype "passive"))
      (node (ref "C9") (pin "2") (pinfunction "2_2") (pintype "passive"))
      (node (ref "D1") (pin "A") (pinfunction "A_A") (pintype "passive"))
      (node (ref "D2") (pin "A") (pinfunction "A_A") (pintype "passive"))
      (node (ref "D5") (pin "A") (pinfunction "A_A") (pintype "passive"))
      (node (ref "IC1") (pin "1") (pinfunction "GND_1") (pintype "bidirectional"))
      (node (ref "IC1") (pin "21") (pinfunction "BLANK_21") (pintype "bidirectional"))
      (node (ref "IC11") (pin "1") (pinfunction "C_1") (pintype "passive"))
      (node (ref "IC2") (pin "2") (pinfunction "GND_2") (pintype "passive"))
      (node (ref "IC3") (pin "6") (pinfunction "INH_6") (pintype "input"))
      (node (ref "IC3") (pin "7") (pinfunction "VEE_7") (pintype "power_in"))
      (node (ref "IC3") (pin "8") (pinfunction "GND_8") (pintype "power_in"))
      (node (ref "IC7") (pin "2") (pinfunction "GND_2") (pintype "passive"))
      (node (ref "IC9") (pin "11") (pinfunction "V-_11") (pintype "power_in"))
      (node (ref "IC9") (pin "12") (pinfunction "+IN_12") (pintype "input"))
      (node (ref "J1") (pin "P1") (pinfunction "1_P1") (pintype "passive"))
      (node (ref "J1") (pin "P2") (pinfunction "2_P2") (pintype "passive"))
      (node (ref "J10") (pin "P1") (pinfunction "1_P1") (pintype "passive"))
      (node (ref "J11") (pin "P1") (pinfunction "1_P1") (pintype "passive"))
      (node (ref "J12") (pin "P1") (pinfunction "1_P1") (pintype "passive"))
      (node (ref "J2") (pin "P1") (pinfunction "1_P1") (pintype "passive"))
      (node (ref "J2") (pin "P2") (pinfunction "2_P2") (pintype "passive"))
      (node (ref "J3") (pin "P1") (pinfunction "1_P1") (pintype "passive"))
      (node (ref "J3") (pin "P2") (pinfunction "2_P2") (pintype "passive"))
      (node (ref "J4") (pin "P1") (pinfunction "1_P1") (pintype "passive"))
      (node (ref "J4") (pin "P2") (pinfunction "2_P2") (pintype "passive"))
      (node (ref "J5") (pin "P1") (pinfunction "1_P1") (pintype "passive"))
      (node (ref "J5") (pin "P2") (pinfunction "2_P2") (pintype "passive"))
      (node (ref "J6") (pin "P1") (pinfunction "1_P1") (pintype "passive"))
      (node (ref "J6") (pin "P2") (pinfunction "2_P2") (pintype "passive"))
      (node (ref "J7") (pin "P1") (pinfunction "1_P1") (pintype "passive"))
      (node (ref "J8") (pin "P1") (pinfunction "1_P1") (pintype "passive"))
      (node (ref "J9") (pin "P1") (pinfunction "1_P1") (pintype "passive"))
      (node (ref "JP6") (pin "1") (pinfunction "1_1") (pintype "passive"))
      (node (ref "JP8") (pin "3") (pinfunction "3_3") (pintype "passive"))
      (node (ref "JP8") (pin "4") (pinfunction "4_4") (pintype "passive"))
      (node (ref "JP8") (pin "5") (pinfunction "5_5") (pintype "passive"))
      (node (ref "JP8") (pin "6") (pinfunction "6_6") (pintype "passive"))
      (node (ref "JP8") (pin "7") (pinfunction "7_7") (pintype "passive"))
      (node (ref "JP8") (pin "8") (pinfunction "8_8") (pintype "passive"))
      (node (ref "POT_A") (pin "P$3") (pinfunction "A_P$3") (pintype "passive"))
      (node (ref "POT_B") (pin "P$3") (pinfunction "A_P$3") (pintype "passive"))
      (node (ref "POT_C") (pin "P$3") (pinfunction "A_P$3") (pintype "passive"))
      (node (ref "Q2") (pin "2") (pinfunction "LID1_2") (pintype "power_in"))
      (node (ref "Q2") (pin "4") (pinfunction "LID2_4") (pintype "power_in"))
      (node (ref "Q5") (pin "E") (pinfunction "E_E") (pintype "passive"))
      (node (ref "Q6") (pin "E") (pinfunction "E_E") (pintype "passive"))
      (node (ref "Q7") (pin "E") (pinfunction "E_E") (pintype "passive"))
      (node (ref "R13") (pin "2") (pinfunction "2_2") (pintype "passive"))
      (node (ref "R17") (pin "2") (pinfunction "2_2") (pintype "passive"))
      (node (ref "R50") (pin "2") (pinfunction "2_2") (pintype "passive"))
      (node (ref "R69") (pin "1") (pinfunction "1_1") (pintype "passive"))
      (node (ref "R70") (pin "1") (pinfunction "1_1") (pintype "passive"))
      (node (ref "R71") (pin "1") (pinfunction "1_1") (pintype "passive"))
      (node (ref "R9") (pin "2") (pinfunction "2_2") (pintype "passive"))
      (node (ref "SLD_A") (pin "1") (pinfunction "A_1") (pintype "passive"))
      (node (ref "SLD_B") (pin "1") (pinfunction "A_1") (pintype "passive"))
      (node (ref "SLD_C") (pin "1") (pinfunction "A_1") (pintype "passive"))
      (node (ref "SW_A") (pin "1") (pinfunction "1_1") (pintype "passive"))
      (node (ref "SW_A") (pin "2") (pinfunction "2_2") (pintype "passive"))
      (node (ref "SW_B") (pin "1") (pinfunction "1_1") (pintype "passive"))
      (node (ref "SW_B") (pin "2") (pinfunction "2_2") (pintype "passive"))
      (node (ref "SW_C") (pin "1") (pinfunction "1_1") (pintype "passive"))
      (node (ref "SW_C") (pin "2") (pinfunction "2_2") (pintype "passive"))
      (node (ref "U$1") (pin "6") (pinfunction "P$6_6") (pintype "bidirectional"))
      (node (ref "U1") (pin "16") (pinfunction "VSS_2_16") (pintype "power_in"))
      (node (ref "U1") (pin "31") (pinfunction "BOOT0_31") (pintype "input"))
      (node (ref "U1") (pin "32") (pinfunction "VSS_1_32") (pintype "power_in"))
      (node (ref "U2") (pin "10") (pinfunction "+IN_10") (pintype "input"))
      (node (ref "U2") (pin "11") (pinfunction "V-_11") (pintype "power_in"))
      (node (ref "U2") (pin "12") (pinfunction "+IN_12") (pintype "input"))
      (node (ref "U2") (pin "3") (pinfunction "+IN_3") (pintype "input"))
      (node (ref "U2") (pin "5") (pinfunction "+IN_5") (pintype "input"))
      (node (ref "U4") (pin "10") (pinfunction "+IN_10") (pintype "input"))
      (node (ref "U4") (pin "12") (pinfunction "+IN_12") (pintype "input"))
      (node (ref "U4") (pin "3") (pinfunction "+IN_3") (pintype "input"))
      (node (ref "U4") (pin "5") (pinfunction "+IN_5") (pintype "input"))
    )
    (net (code "24") (name "LEDS_SCK") (class "Default")
      (node (ref "IC1") (pin "3") (pinfunction "SCLK_3") (pintype "bidirectional"))
      (node (ref "U1") (pin "26") (pinfunction "PB3_26") (pintype "bidirectional"))
    )
    (net (code "25") (name "LEDS_SIN") (class "Default")
      (node (ref "IC1") (pin "2") (pinfunction "SIN_2") (pintype "bidirectional"))
      (node (ref "U1") (pin "28") (pinfunction "PB5_28") (pintype "bidirectional"))
    )
    (net (code "26") (name "N_U") (class "Default")
      (node (ref "U2") (pin "6") (pinfunction "-IN_6") (pintype "input"))
      (node (ref "U2") (pin "7") (pinfunction "OUT_7") (pintype "output"))
    )
    (net (code "27") (name "Net-(C13-Pad1)") (class "Default")
      (node (ref "C13") (pin "1") (pinfunction "1_1") (pintype "passive"))
      (node (ref "D3") (pin "C") (pinfunction "C_C") (pintype "passive"))
      (node (ref "L3") (pin "1") (pinfunction "1_1") (pintype "passive"))
      (node (ref "L4") (pin "2") (pinfunction "2_2") (pintype "passive"))
      (node (ref "L5") (pin "2") (pinfunction "2_2") (pintype "passive"))
    )
    (net (code "28") (name "Net-(C34-Pad2)") (class "Default")
      (node (ref "C34") (pin "2") (pinfunction "2_2") (pintype "passive"))
      (node (ref "Q2") (pin "1") (pinfunction "1_1") (pintype "passive"))
      (node (ref "R22") (pin "2") (pinfunction "2_2") (pintype "passive"))
    )
    (net (code "29") (name "Net-(D1-PadC)") (class "Default")
      (node (ref "D1") (pin "C") (pinfunction "C_C") (pintype "passive"))
      (node (ref "Q7") (pin "B") (pinfunction "B_B") (pintype "passive"))
      (node (ref "R66") (pin "2") (pinfunction "2_2") (pintype "passive"))
      (node (ref "R69") (pin "2") (pinfunction "2_2") (pintype "passive"))
    )
    (net (code "30") (name "Net-(D2-PadC)") (class "Default")
      (node (ref "D2") (pin "C") (pinfunction "C_C") (pintype "passive"))
      (node (ref "Q5") (pin "B") (pinfunction "B_B") (pintype "passive"))
      (node (ref "R67") (pin "2") (pinfunction "2_2") (pintype "passive"))
      (node (ref "R70") (pin "2") (pinfunction "2_2") (pintype "passive"))
    )
    (net (code "31") (name "Net-(D4-PadA)") (class "Default")
      (node (ref "D4") (pin "A") (pinfunction "A_A") (pintype "passive"))
      (node (ref "L1") (pin "2") (pinfunction "2_2") (pintype "passive"))
    )
    (net (code "32") (name "Net-(D5-PadC)") (class "Default")
      (node (ref "D5") (pin "C") (pinfunction "C_C") (pintype "passive"))
      (node (ref "Q6") (pin "B") (pinfunction "B_B") (pintype "passive"))
      (node (ref "R68") (pin "2") (pinfunction "2_2") (pintype "passive"))
      (node (ref "R71") (pin "2") (pinfunction "2_2") (pintype "passive"))
    )
    (net (code "33") (name "Net-(IC1-IREF)") (class "Default")
      (node (ref "IC1") (pin "23") (pinfunction "IREF_23") (pintype "bidirectional"))
      (node (ref "R50") (pin "1") (pinfunction "1_1") (pintype "passive"))
    )
    (net (code "34") (name "Net-(IC1-OUT1)") (class "Default")
      (node (ref "IC1") (pin "6") (pinfunction "OUT1_6") (pintype "bidirectional"))
      (node (ref "R31") (pin "2") (pinfunction "2_2") (pintype "passive"))
    )
    (net (code "35") (name "Net-(IC1-OUT2)") (class "Default")
      (node (ref "IC1") (pin "7") (pinfunction "OUT2_7") (pintype "bidirectional"))
      (node (ref "MODE_C") (pin "RED_C") (pinfunction "RED_RED_C") (pintype "bidirectional"))
    )
    (net (code "36") (name "Net-(IC1-OUT3)") (class "Default")
      (node (ref "IC1") (pin "8") (pinfunction "OUT3_8") (pintype "bidirectional"))
      (node (ref "MODE_C") (pin "GREEN_C") (pinfunction "GRN_GREEN_C") (pintype "bidirectional"))
    )
    (net (code "37") (name "Net-(IC1-OUT4)") (class "Default")
      (node (ref "IC1") (pin "9") (pinfunction "OUT4_9") (pintype "bidirectional"))
      (node (ref "MODE_A") (pin "GREEN_C") (pinfunction "GRN_GREEN_C") (pintype "bidirectional"))
    )
    (net (code "38") (name "Net-(IC1-OUT5)") (class "Default")
      (node (ref "IC1") (pin "10") (pinfunction "OUT5_10") (pintype "bidirectional"))
      (node (ref "MODE_A") (pin "RED_C") (pinfunction "RED_RED_C") (pintype "bidirectional"))
    )
    (net (code "39") (name "Net-(IC1-OUT6)") (class "Default")
      (node (ref "IC1") (pin "11") (pinfunction "OUT6_11") (pintype "bidirectional"))
      (node (ref "MODE_B") (pin "GREEN_C") (pinfunction "GRN_GREEN_C") (pintype "bidirectional"))
    )
    (net (code "40") (name "Net-(IC1-OUT7)") (class "Default")
      (node (ref "IC1") (pin "12") (pinfunction "OUT7_12") (pintype "bidirectional"))
      (node (ref "MODE_B") (pin "RED_C") (pinfunction "RED_RED_C") (pintype "bidirectional"))
    )
    (net (code "41") (name "Net-(IC1-OUT8)") (class "Default")
      (node (ref "IC1") (pin "13") (pinfunction "OUT8_13") (pintype "bidirectional"))
      (node (ref "LED10") (pin "GREEN_C") (pinfunction "GRN_GREEN_C") (pintype "bidirectional"))
    )
    (net (code "42") (name "Net-(IC1-OUT9)") (class "Default")
      (node (ref "IC1") (pin "14") (pinfunction "OUT9_14") (pintype "bidirectional"))
      (node (ref "LED10") (pin "RED_C") (pinfunction "RED_RED_C") (pintype "bidirectional"))
    )
    (net (code "43") (name "Net-(IC1-OUT10)") (class "Default")
      (node (ref "IC1") (pin "15") (pinfunction "OUT10_15") (pintype "bidirectional"))
      (node (ref "LED11") (pin "RED_C") (pinfunction "RED_RED_C") (pintype "bidirectional"))
    )
    (net (code "44") (name "Net-(IC1-OUT11)") (class "Default")
      (node (ref "IC1") (pin "16") (pinfunction "OUT11_16") (pintype "bidirectional"))
      (node (ref "LED11") (pin "GREEN_C") (pinfunction "GRN_GREEN_C") (pintype "bidirectional"))
    )
    (net (code "45") (name "Net-(IC1-OUT12)") (class "Default")
      (node (ref "IC1") (pin "17") (pinfunction "OUT12_17") (pintype "bidirectional"))
      (node (ref "LED12") (pin "RED_C") (pinfunction "RED_RED_C") (pintype "bidirectional"))
    )
    (net (code "46") (name "Net-(IC1-OUT13)") (class "Default")
      (node (ref "IC1") (pin "18") (pinfunction "OUT13_18") (pintype "bidirectional"))
      (node (ref "LED12") (pin "GREEN_C") (pinfunction "GRN_GREEN_C") (pintype "bidirectional"))
    )
    (net (code "47") (name "Net-(IC1-OUT14)") (class "Default")
      (node (ref "IC1") (pin "19") (pinfunction "OUT14_19") (pintype "bidirectional"))
      (node (ref "R19") (pin "2") (pinfunction "2_2") (pintype "passive"))
    )
    (net (code "48") (name "Net-(IC1-OUT15)") (class "Default")
      (node (ref "IC1") (pin "20") (pinfunction "OUT15_20") (pintype "bidirectional"))
      (node (ref "R30") (pin "2") (pinfunction "2_2") (pintype "passive"))
    )
    (net (code "49") (name "Net-(IC1-VCC)") (class "Default")
      (node (ref "C7") (pin "1") (pinfunction "1_1") (pintype "passive"))
      (node (ref "C8") (pin "1") (pinfunction "1_1") (pintype "passive"))
      (node (ref "IC1") (pin "24") (pinfunction "VCC_24") (pintype "bidirectional"))
      (node (ref "L2") (pin "1") (pinfunction "1_1") (pintype "passive"))
    )
    (net (code "50") (name "Net-(IC2-VI)") (class "Default")
      (node (ref "C15") (pin "1") (pinfunction "1_1") (pintype "passive"))
      (node (ref "IC2") (pin "1") (pinfunction "VI_1") (pintype "input"))
      (node (ref "L3") (pin "2") (pinfunction "2_2") (pintype "passive"))
    )
    (net (code "51") (name "Net-(IC3A-X0)") (class "Default")
      (node (ref "IC3") (pin "13") (pinfunction "X0_13") (pintype "bidirectional"))
      (node (ref "POT_C") (pin "P$2") (pinfunction "S_P$2") (pintype "passive"))
    )
    (net (code "52") (name "Net-(IC3A-X1)") (class "Default")
      (node (ref "IC3") (pin "14") (pinfunction "X1_14") (pintype "bidirectional"))
      (node (ref "SLD_C") (pin "2") (pinfunction "S_2") (pintype "passive"))
    )
    (net (code "53") (name "Net-(IC3A-X2)") (class "Default")
      (node (ref "IC3") (pin "15") (pinfunction "X2_15") (pintype "bidirectional"))
      (node (ref "SLD_B") (pin "2") (pinfunction "S_2") (pintype "passive"))
    )
    (net (code "54") (name "Net-(IC3A-X3)") (class "Default")
      (node (ref "IC3") (pin "12") (pinfunction "X3_12") (pintype "bidirectional"))
      (node (ref "POT_A") (pin "P$2") (pinfunction "S_P$2") (pintype "passive"))
    )
    (net (code "55") (name "Net-(IC3A-X4)") (class "Default")
      (node (ref "IC3") (pin "1") (pinfunction "X4_1") (pintype "bidirectional"))
      (node (ref "SLD_A") (pin "2") (pinfunction "S_2") (pintype "passive"))
    )
    (net (code "56") (name "Net-(IC3A-X6)") (class "Default")
      (node (ref "IC3") (pin "2") (pinfunction "X6_2") (pintype "bidirectional"))
      (node (ref "POT_B") (pin "P$2") (pinfunction "S_P$2") (pintype "passive"))
    )
    (net (code "57") (name "Net-(IC7-VI)") (class "Default")
      (node (ref "C20") (pin "1") (pinfunction "1_1") (pintype "passive"))
      (node (ref "IC7") (pin "3") (pinfunction "VI_3") (pintype "input"))
      (node (ref "L4") (pin "1") (pinfunction "1_1") (pintype "passive"))
    )
    (net (code "58") (name "Net-(IC9A-+IN)") (class "Default")
      (node (ref "IC9") (pin "3") (pinfunction "+IN_3") (pintype "input"))
      (node (ref "R8") (pin "2") (pinfunction "2_2") (pintype "passive"))
      (node (ref "R9") (pin "1") (pinfunction "1_1") (pintype "passive"))
    )
    (net (code "59") (name "Net-(IC9A--IN)") (class "Default")
      (node (ref "IC9") (pin "2") (pinfunction "-IN_2") (pintype "input"))
      (node (ref "R10") (pin "1") (pinfunction "1_1") (pintype "passive"))
    )
    (net (code "60") (name "Net-(IC9A-OUT)") (class "Default")
      (node (ref "IC9") (pin "1") (pinfunction "OUT_1") (pintype "output"))
      (node (ref "R7") (pin "2") (pinfunction "2_2") (pintype "passive"))
      (node (ref "R8") (pin "1") (pinfunction "1_1") (pintype "passive"))
    )
    (net (code "61") (name "Net-(IC9B-+IN)") (class "Default")
      (node (ref "IC9") (pin "5") (pinfunction "+IN_5") (pintype "input"))
      (node (ref "R12") (pin "2") (pinfunction "2_2") (pintype "passive"))
      (node (ref "R13") (pin "1") (pinfunction "1_1") (pintype "passive"))
    )
    (net (code "62") (name "Net-(IC9B--IN)") (class "Default")
      (node (ref "IC9") (pin "6") (pinfunction "-IN_6") (pintype "input"))
      (node (ref "R14") (pin "1") (pinfunction "1_1") (pintype "passive"))
    )
    (net (code "63") (name "Net-(IC9B-OUT)") (class "Default")
      (node (ref "IC9") (pin "7") (pinfunction "OUT_7") (pintype "output"))
      (node (ref "R11") (pin "2") (pinfunction "2_2") (pintype "passive"))
      (node (ref "R12") (pin "1") (pinfunction "1_1") (pintype "passive"))
    )
    (net (code "64") (name "Net-(IC9C-+IN)") (class "Default")
      (node (ref "IC9") (pin "10") (pinfunction "+IN_10") (pintype "input"))
      (node (ref "R16") (pin "2") (pinfunction "2_2") (pintype "passive"))
      (node (ref "R17") (pin "1") (pinfunction "1_1") (pintype "passive"))
    )
    (net (code "65") (name "Net-(IC9C--IN)") (class "Default")
      (node (ref "IC9") (pin "9") (pinfunction "-IN_9") (pintype "input"))
      (node (ref "R20") (pin "1") (pinfunction "1_1") (pintype "passive"))
    )
    (net (code "66") (name "Net-(IC9C-OUT)") (class "Default")
      (node (ref "IC9") (pin "8") (pinfunction "OUT_8") (pintype "output"))
      (node (ref "R15") (pin "2") (pinfunction "2_2") (pintype "passive"))
      (node (ref "R16") (pin "1") (pinfunction "1_1") (pintype "passive"))
    )
    (net (code "67") (name "Net-(IC9D--IN)") (class "Default")
      (node (ref "IC9") (pin "13") (pinfunction "-IN_13") (pintype "input"))
      (node (ref "IC9") (pin "14") (pinfunction "OUT_14") (pintype "output"))
    )
    (net (code "68") (name "Net-(J2-3)") (class "Default")
      (node (ref "J2") (pin "P3") (pinfunction "3_P3") (pintype "passive"))
      (node (ref "R4") (pin "2") (pinfunction "2_2") (pintype "passive"))
    )
    (net (code "69") (name "Net-(J5-3)") (class "Default")
      (node (ref "J5") (pin "P3") (pinfunction "3_P3") (pintype "passive"))
      (node (ref "R51") (pin "2") (pinfunction "2_2") (pintype "passive"))
    )
    (net (code "70") (name "Net-(J7-3)") (class "Default")
      (node (ref "J7") (pin "P3") (pinfunction "3_P3") (pintype "passive"))
      (node (ref "R27") (pin "1") (pinfunction "1_1") (pintype "passive"))
      (node (ref "R32") (pin "1") (pinfunction "1_1") (pintype "passive"))
    )
    (net (code "71") (name "Net-(J8-3)") (class "Default")
      (node (ref "J8") (pin "P3") (pinfunction "3_P3") (pintype "passive"))
      (node (ref "R23") (pin "1") (pinfunction "1_1") (pintype "passive"))
      (node (ref "R3") (pin "1") (pinfunction "1_1") (pintype "passive"))
    )
    (net (code "72") (name "Net-(J9-3)") (class "Default")
      (node (ref "J9") (pin "P3") (pinfunction "3_P3") (pintype "passive"))
      (node (ref "R35") (pin "1") (pinfunction "1_1") (pintype "passive"))
      (node (ref "R41") (pin "1") (pinfunction "1_1") (pintype "passive"))
    )
    (net (code "73") (name "Net-(J10-3)") (class "Default")
      (node (ref "J10") (pin "P3") (pinfunction "3_P3") (pintype "passive"))
      (node (ref "R11") (pin "1") (pinfunction "1_1") (pintype "passive"))
    )
    (net (code "74") (name "Net-(J11-3)") (class "Default")
      (node (ref "J11") (pin "P3") (pinfunction "3_P3") (pintype "passive"))
      (node (ref "R15") (pin "1") (pinfunction "1_1") (pintype "passive"))
    )
    (net (code "75") (name "Net-(J12-3)") (class "Default")
      (node (ref "J12") (pin "P3") (pinfunction "3_P3") (pintype "passive"))
      (node (ref "R7") (pin "1") (pinfunction "1_1") (pintype "passive"))
    )
    (net (code "76") (name "Net-(Q2B-2)") (class "Default")
      (node (ref "C35") (pin "2") (pinfunction "2_2") (pintype "passive"))
      (node (ref "Q2") (pin "3") (pinfunction "2_3") (pintype "passive"))
      (node (ref "R21") (pin "2") (pinfunction "2_2") (pintype "passive"))
    )
    (net (code "77") (name "Net-(SLD_AA-C)") (class "Default")
      (node (ref "R19") (pin "1") (pinfunction "1_1") (pintype "passive"))
      (node (ref "SLD_A") (pin "E") (pinfunction "C_E") (pintype "passive"))
    )
    (net (code "78") (name "Net-(SLD_BA-C)") (class "Default")
      (node (ref "R30") (pin "1") (pinfunction "1_1") (pintype "passive"))
      (node (ref "SLD_B") (pin "E") (pinfunction "C_E") (pintype "passive"))
    )
    (net (code "79") (name "Net-(SLD_CA-C)") (class "Default")
      (node (ref "R31") (pin "1") (pinfunction "1_1") (pintype "passive"))
      (node (ref "SLD_C") (pin "E") (pinfunction "C_E") (pintype "passive"))
    )
    (net (code "80") (name "Net-(U1-PF0{slash}OSC_IN)") (class "Default")
      (node (ref "R21") (pin "1") (pinfunction "1_1") (pintype "passive"))
      (node (ref "U1") (pin "2") (pinfunction "PF0/OSC_IN_2") (pintype "bidirectional"))
    )
    (net (code "81") (name "Net-(U1-PF1{slash}OSC_OUT)") (class "Default")
      (node (ref "R22") (pin "1") (pinfunction "1_1") (pintype "passive"))
      (node (ref "U1") (pin "3") (pinfunction "PF1/OSC_OUT_3") (pintype "bidirectional"))
    )
    (net (code "82") (name "Net-(U2A--IN)") (class "Default")
      (node (ref "C12") (pin "1") (pinfunction "1_1") (pintype "passive"))
      (node (ref "R29") (pin "1") (pinfunction "1_1") (pintype "passive"))
      (node (ref "R4") (pin "1") (pinfunction "1_1") (pintype "passive"))
      (node (ref "R5") (pin "2") (pinfunction "2_2") (pintype "passive"))
      (node (ref "U2") (pin "2") (pinfunction "-IN_2") (pintype "input"))
    )
    (net (code "83") (name "Net-(U2C--IN)") (class "Default")
      (node (ref "C26") (pin "1") (pinfunction "1_1") (pintype "passive"))
      (node (ref "R26") (pin "2") (pinfunction "2_2") (pintype "passive"))
      (node (ref "R28") (pin "1") (pinfunction "1_1") (pintype "passive"))
      (node (ref "R6") (pin "1") (pinfunction "1_1") (pintype "passive"))
      (node (ref "U2") (pin "9") (pinfunction "-IN_9") (pintype "input"))
    )
    (net (code "84") (name "Net-(U2D--IN)") (class "Default")
      (node (ref "C28") (pin "1") (pinfunction "1_1") (pintype "passive"))
      (node (ref "R51") (pin "1") (pinfunction "1_1") (pintype "passive"))
      (node (ref "R52") (pin "2") (pinfunction "2_2") (pintype "passive"))
      (node (ref "R53") (pin "1") (pinfunction "1_1") (pintype "passive"))
      (node (ref "U2") (pin "13") (pinfunction "-IN_13") (pintype "input"))
    )
    (net (code "85") (name "Net-(U4A--IN)") (class "Default")
      (node (ref "C1") (pin "1") (pinfunction "1_1") (pintype "passive"))
      (node (ref "R2") (pin "1") (pinfunction "1_1") (pintype "passive"))
      (node (ref "R41") (pin "2") (pinfunction "2_2") (pintype "passive"))
      (node (ref "R47") (pin "1") (pinfunction "1_1") (pintype "passive"))
      (node (ref "U4") (pin "2") (pinfunction "-IN_2") (pintype "input"))
    )
    (net (code "86") (name "Net-(U4A-OUT)") (class "Default")
      (node (ref "C1") (pin "2") (pinfunction "2_2") (pintype "passive"))
      (node (ref "R35") (pin "2") (pinfunction "2_2") (pintype "passive"))
      (node (ref "U4") (pin "1") (pinfunction "OUT_1") (pintype "output"))
    )
    (net (code "87") (name "Net-(U4B--IN)") (class "Default")
      (node (ref "C2") (pin "1") (pinfunction "1_1") (pintype "passive"))
      (node (ref "R23") (pin "2") (pinfunction "2_2") (pintype "passive"))
      (node (ref "R24") (pin "1") (pinfunction "1_1") (pintype "passive"))
      (node (ref "R25") (pin "1") (pinfunction "1_1") (pintype "passive"))
      (node (ref "U4") (pin "6") (pinfunction "-IN_6") (pintype "input"))
    )
    (net (code "88") (name "Net-(U4B-OUT)") (class "Default")
      (node (ref "C2") (pin "2") (pinfunction "2_2") (pintype "passive"))
      (node (ref "R3") (pin "2") (pinfunction "2_2") (pintype "passive"))
      (node (ref "U4") (pin "7") (pinfunction "OUT_7") (pintype "output"))
    )
    (net (code "89") (name "Net-(U4C--IN)") (class "Default")
      (node (ref "C3") (pin "1") (pinfunction "1_1") (pintype "passive"))
      (node (ref "R32") (pin "2") (pinfunction "2_2") (pintype "passive"))
      (node (ref "R33") (pin "1") (pinfunction "1_1") (pintype "passive"))
      (node (ref "R34") (pin "1") (pinfunction "1_1") (pintype "passive"))
      (node (ref "U4") (pin "9") (pinfunction "-IN_9") (pintype "input"))
    )
    (net (code "90") (name "Net-(U4C-OUT)") (class "Default")
      (node (ref "C3") (pin "2") (pinfunction "2_2") (pintype "passive"))
      (node (ref "R27") (pin "2") (pinfunction "2_2") (pintype "passive"))
      (node (ref "U4") (pin "8") (pinfunction "OUT_8") (pintype "output"))
    )
    (net (code "91") (name "Net-(U4D--IN)") (class "Default")
      (node (ref "U4") (pin "13") (pinfunction "-IN_13") (pintype "input"))
      (node (ref "U4") (pin "14") (pinfunction "OUT_14") (pintype "output"))
    )
    (net (code "92") (name "POTS_ADDR_A") (class "Default")
      (node (ref "IC3") (pin "11") (pinfunction "A_11") (pintype "input"))
      (node (ref "U1") (pin "13") (pinfunction "PA7_13") (pintype "bidirectional"))
    )
    (net (code "93") (name "POTS_ADDR_B") (class "Default")
      (node (ref "IC3") (pin "10") (pinfunction "B_10") (pintype "input"))
      (node (ref "U1") (pin "18") (pinfunction "PA8_18") (pintype "bidirectional"))
    )
    (net (code "94") (name "POTS_ADDR_C") (class "Default")
      (node (ref "IC3") (pin "9") (pinfunction "C_9") (pintype "input"))
      (node (ref "U1") (pin "19") (pinfunction "PA9_19") (pintype "bidirectional"))
    )
    (net (code "95") (name "RESET") (class "Default")
      (node (ref "C36") (pin "1") (pinfunction "1_1") (pintype "passive"))
      (node (ref "JP6") (pin "4") (pinfunction "4_4") (pintype "passive"))
      (node (ref "R18") (pin "2") (pinfunction "2_2") (pintype "passive"))
      (node (ref "U1") (pin "4") (pinfunction "NRST_4") (pintype "bidirectional"))
    )
    (net (code "96") (name "SWCLK") (class "Default")
      (node (ref "JP6") (pin "3") (pinfunction "3_3") (pintype "passive"))
      (node (ref "U1") (pin "24") (pinfunction "PA14_24") (pintype "bidirectional"))
    )
    (net (code "97") (name "SWDIO") (class "Default")
      (node (ref "JP6") (pin "2") (pinfunction "2_2") (pintype "passive"))
      (node (ref "U1") (pin "23") (pinfunction "PA13_23") (pintype "bidirectional"))
    )
    (net (code "98") (name "SW_MODE_A") (class "Default")
      (node (ref "SW_A") (pin "3") (pinfunction "3_3") (pintype "passive"))
      (node (ref "SW_A") (pin "4") (pinfunction "4_4") (pintype "passive"))
      (node (ref "U1") (pin "27") (pinfunction "PB4_27") (pintype "bidirectional"))
    )
    (net (code "99") (name "SW_MODE_B") (class "Default")
      (node (ref "SW_B") (pin "3") (pinfunction "3_3") (pintype "passive"))
      (node (ref "SW_B") (pin "4") (pinfunction "4_4") (pintype "passive"))
      (node (ref "U1") (pin "29") (pinfunction "PB6_29") (pintype "bidirectional"))
    )
    (net (code "100") (name "SW_MODE_C") (class "Default")
      (node (ref "SW_C") (pin "3") (pinfunction "3_3") (pintype "passive"))
      (node (ref "SW_C") (pin "4") (pinfunction "4_4") (pintype "passive"))
      (node (ref "U1") (pin "30") (pinfunction "PB7_30") (pintype "bidirectional"))
    )
    (net (code "101") (name "VCC") (class "Default")
      (node (ref "C14") (pin "1") (pinfunction "1_1") (pintype "passive"))
      (node (ref "C21") (pin "1") (pinfunction "1_1") (pintype "passive"))
      (node (ref "C4") (pin "1") (pinfunction "1_1") (pintype "passive"))
      (node (ref "C50") (pin "1") (pinfunction "1_1") (pintype "passive"))
      (node (ref "IC9") (pin "4") (pinfunction "V+_4") (pintype "power_in"))
      (node (ref "L5") (pin "1") (pinfunction "1_1") (pintype "passive"))
      (node (ref "U$1") (pin "1") (pinfunction "P$1_1") (pintype "bidirectional"))
      (node (ref "U4") (pin "4") (pinfunction "V+_4") (pintype "power_in"))
    )
    (net (code "102") (name "VEE") (class "Default")
      (node (ref "C16") (pin "2") (pinfunction "2_2") (pintype "passive"))
      (node (ref "C18") (pin "2") (pinfunction "2_2") (pintype "passive"))
      (node (ref "C23") (pin "2") (pinfunction "2_2") (pintype "passive"))
      (node (ref "L1") (pin "1") (pinfunction "1_1") (pintype "passive"))
      (node (ref "R1") (pin "1") (pinfunction "1_1") (pintype "passive"))
      (node (ref "U$1") (pin "2") (pinfunction "P$2_2") (pintype "bidirectional"))
      (node (ref "U4") (pin "11") (pinfunction "V-_11") (pintype "power_in"))
    )
    (net (code "103") (name "unconnected-(IC1-LAT-Pad4)") (class "Default")
      (node (ref "IC1") (pin "4") (pinfunction "LAT_4") (pintype "bidirectional"))
    )
    (net (code "104") (name "unconnected-(IC1-OUT0-Pad5)") (class "Default")
      (node (ref "IC1") (pin "5") (pinfunction "OUT0_5") (pintype "bidirectional"))
    )
    (net (code "105") (name "unconnected-(IC1-SOUT-Pad22)") (class "Default")
      (node (ref "IC1") (pin "22") (pinfunction "SOUT_22") (pintype "bidirectional"))
    )
    (net (code "106") (name "unconnected-(IC3A-X5-Pad5)") (class "Default")
      (node (ref "IC3") (pin "5") (pinfunction "X5_5") (pintype "bidirectional"))
    )
    (net (code "107") (name "unconnected-(IC3A-X7-Pad4)") (class "Default")
      (node (ref "IC3") (pin "4") (pinfunction "X7_4") (pintype "bidirectional"))
    )
    (net (code "108") (name "unconnected-(J7-2-PadP2)") (class "Default")
      (node (ref "J7") (pin "P2") (pinfunction "2_P2") (pintype "passive"))
    )
    (net (code "109") (name "unconnected-(J8-2-PadP2)") (class "Default")
      (node (ref "J8") (pin "P2") (pinfunction "2_P2") (pintype "passive"))
    )
    (net (code "110") (name "unconnected-(J9-2-PadP2)") (class "Default")
      (node (ref "J9") (pin "P2") (pinfunction "2_P2") (pintype "passive"))
    )
    (net (code "111") (name "unconnected-(J10-2-PadP2)") (class "Default")
      (node (ref "J10") (pin "P2") (pinfunction "2_P2") (pintype "passive"))
    )
    (net (code "112") (name "unconnected-(J11-2-PadP2)") (class "Default")
      (node (ref "J11") (pin "P2") (pinfunction "2_P2") (pintype "passive"))
    )
    (net (code "113") (name "unconnected-(J12-2-PadP2)") (class "Default")
      (node (ref "J12") (pin "P2") (pinfunction "2_P2") (pintype "passive"))
    )
  )
)
